# 2.net
KiCad netlist of a schematic drawn in EAGLE
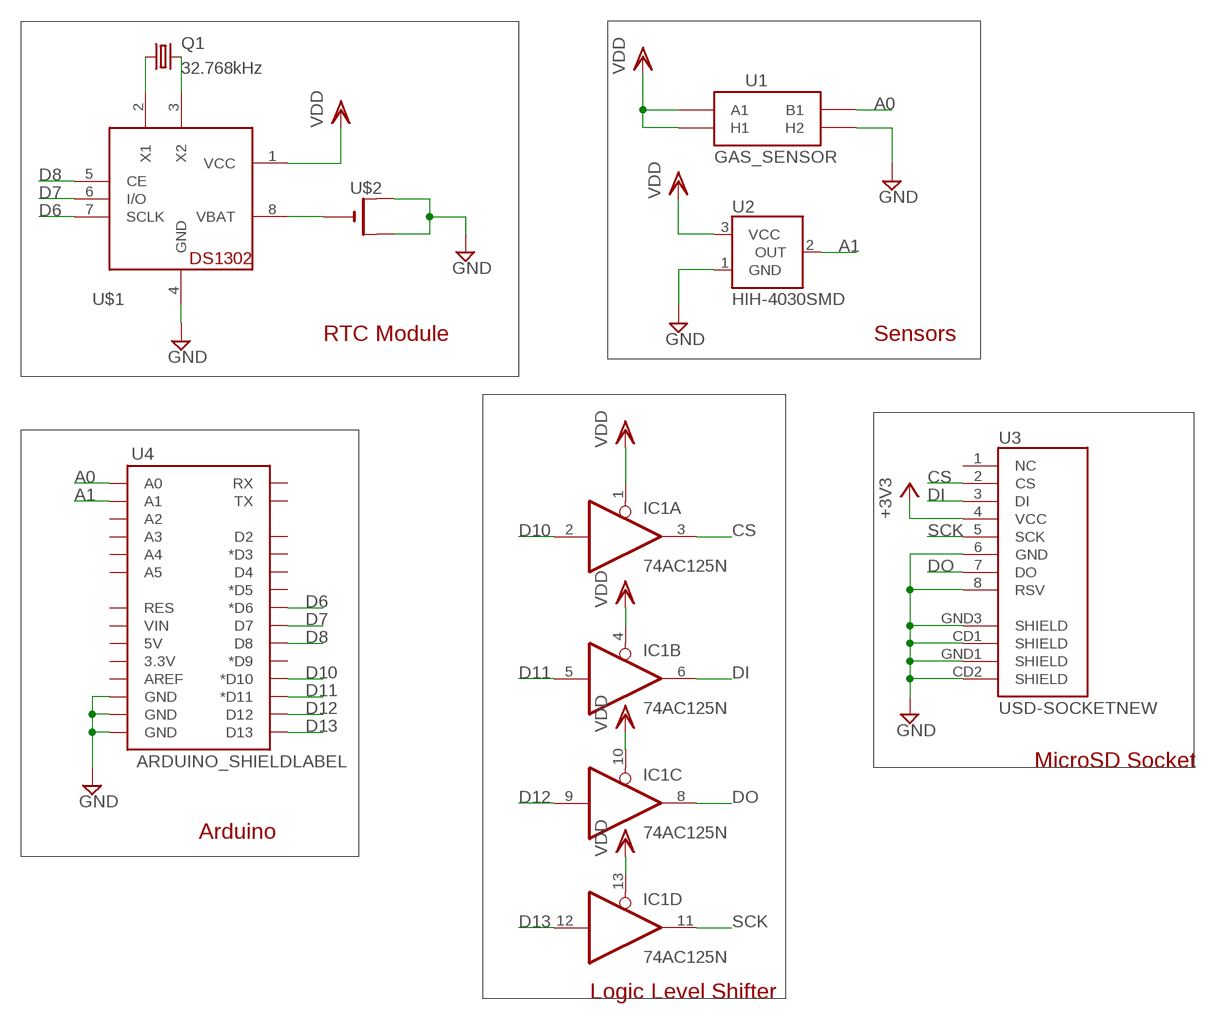
[diagram p0: schematic, sheet 1]

(export (version "E")
  (design (tool "Eeschema 10.0.6"))
  (components
    (comp (ref "IC1")
      (value "74AC125N")
      (footprint "eagle-import:DIL14")
      (libsource (lib "eagle-import") (part "74125NAC"))
    )
    (comp (ref "Q1")
      (value "32.768kHz")
      (footprint "eagle-import:TC38H")
      (libsource (lib "eagle-import") (part "CRYSTALTC38H"))
    )
    (comp (ref "U$1")
      (value "DS1302")
      (footprint "eagle-import:DIL08-ROUND")
      (libsource (lib "eagle-import") (part "DS1302"))
    )
    (comp (ref "U$2")
      (value "CR2032THM")
      (footprint "eagle-import:CR2032-THRU")
      (libsource (lib "eagle-import") (part "CR2032THM"))
    )
    (comp (ref "U1")
      (value "GAS_SENSOR")
      (footprint "eagle-import:MQ-3")
      (libsource (lib "eagle-import") (part "GAS_SENSOR"))
    )
    (comp (ref "U2")
      (value "HIH-4030SMD")
      (footprint "eagle-import:HIH-4030")
      (libsource (lib "eagle-import") (part "HIH-4030SMD"))
    )
    (comp (ref "U3")
      (value "USD-SOCKETNEW")
      (footprint "eagle-import:MICRO-SD-SOCKET-PP")
      (libsource (lib "eagle-import") (part "USD-SOCKETNEW"))
    )
    (comp (ref "U4")
      (value "ARDUINO_SHIELDLABEL")
      (footprint "eagle-import:DUEMILANOVE_SHIELD")
      (libsource (lib "eagle-import") (part "ARDUINO_SHIELDLABEL"))
    )
  )
  (nets
    (net (code "1") (name "+3V3") (class "Default")
      (node (ref "U3") (pin "4") (pinfunction "VCC_4") (pintype "bidirectional"))
    )
    (net (code "2") (name "/A0") (class "Default")
      (node (ref "U1") (pin "B1") (pinfunction "B1_B1") (pintype "bidirectional"))
      (node (ref "U4") (pin "A0") (pinfunction "A0_A0") (pintype "bidirectional"))
    )
    (net (code "3") (name "/A1") (class "Default")
      (node (ref "U2") (pin "2") (pinfunction "OUT_2") (pintype "bidirectional"))
      (node (ref "U4") (pin "A1") (pinfunction "A1_A1") (pintype "bidirectional"))
    )
    (net (code "4") (name "/CS") (class "Default")
      (node (ref "IC1") (pin "3") (pinfunction "O_3") (pintype "tri_state"))
      (node (ref "U3") (pin "2") (pinfunction "CS_2") (pintype "bidirectional"))
    )
    (net (code "5") (name "/D6") (class "Default")
      (node (ref "U$1") (pin "7") (pinfunction "SCLK_7") (pintype "input"))
      (node (ref "U4") (pin "D6") (pinfunction "*D6_D6") (pintype "bidirectional"))
    )
    (net (code "6") (name "/D7") (class "Default")
      (node (ref "U$1") (pin "6") (pinfunction "I/O_6") (pintype "bidirectional"))
      (node (ref "U4") (pin "D7") (pinfunction "D7_D7") (pintype "bidirectional"))
    )
    (net (code "7") (name "/D8") (class "Default")
      (node (ref "U$1") (pin "5") (pinfunction "CE_5") (pintype "input"))
      (node (ref "U4") (pin "D8") (pinfunction "D8_D8") (pintype "bidirectional"))
    )
    (net (code "8") (name "/D10") (class "Default")
      (node (ref "IC1") (pin "2") (pinfunction "I_2") (pintype "input"))
      (node (ref "U4") (pin "D10") (pinfunction "*D10_D10") (pintype "bidirectional"))
    )
    (net (code "9") (name "/D11") (class "Default")
      (node (ref "IC1") (pin "5") (pinfunction "I_5") (pintype "input"))
      (node (ref "U4") (pin "D11") (pinfunction "*D11_D11") (pintype "bidirectional"))
    )
    (net (code "10") (name "/D12") (class "Default")
      (node (ref "IC1") (pin "9") (pinfunction "I_9") (pintype "input"))
      (node (ref "U4") (pin "D12") (pinfunction "D12_D12") (pintype "bidirectional"))
    )
    (net (code "11") (name "/D13") (class "Default")
      (node (ref "IC1") (pin "12") (pinfunction "I_12") (pintype "input"))
      (node (ref "U4") (pin "D13") (pinfunction "D13_D13") (pintype "bidirectional"))
    )
    (net (code "12") (name "/DI") (class "Default")
      (node (ref "IC1") (pin "6") (pinfunction "O_6") (pintype "tri_state"))
      (node (ref "U3") (pin "3") (pinfunction "DI_3") (pintype "bidirectional"))
    )
    (net (code "13") (name "/DO") (class "Default")
      (node (ref "IC1") (pin "8") (pinfunction "O_8") (pintype "tri_state"))
      (node (ref "U3") (pin "7") (pinfunction "DO_7") (pintype "bidirectional"))
    )
    (net (code "14") (name "/SCK") (class "Default")
      (node (ref "IC1") (pin "11") (pinfunction "O_11") (pintype "tri_state"))
      (node (ref "U3") (pin "5") (pinfunction "SCK_5") (pintype "bidirectional"))
    )
    (net (code "15") (name "GND") (class "Default")
      (node (ref "U$1") (pin "4") (pinfunction "GND_4") (pintype "power_in"))
      (node (ref "U$2") (pin "+1") (pinfunction "+_+1") (pintype "passive"))
      (node (ref "U$2") (pin "+2") (pinfunction "+1_+2") (pintype "passive"))
      (node (ref "U1") (pin "HB") (pinfunction "H2_HB") (pintype "bidirectional"))
      (node (ref "U2") (pin "1") (pinfunction "GND_1") (pintype "bidirectional"))
      (node (ref "U3") (pin "6") (pinfunction "GND_6") (pintype "bidirectional"))
      (node (ref "U3") (pin "8") (pinfunction "RSV_8") (pintype "bidirectional"))
      (node (ref "U3") (pin "CD1") (pinfunction "SHIELD_CD1") (pintype "bidirectional"))
      (node (ref "U3") (pin "CD2") (pinfunction "SHIELD_CD2") (pintype "bidirectional"))
      (node (ref "U3") (pin "GND1") (pinfunction "SHIELD_GND1") (pintype "bidirectional"))
      (node (ref "U3") (pin "GND3") (pinfunction "SHIELD_GND3") (pintype "bidirectional"))
      (node (ref "U4") (pin "GND@0") (pinfunction "GND_GND@0") (pintype "bidirectional"))
      (node (ref "U4") (pin "GND@1") (pinfunction "GND_GND@1") (pintype "bidirectional"))
      (node (ref "U4") (pin "GND@2") (pinfunction "GND_GND@2") (pintype "bidirectional"))
    )
    (net (code "16") (name "Net-(U$1-VBAT)") (class "Default")
      (node (ref "U$1") (pin "8") (pinfunction "VBAT_8") (pintype "power_in"))
      (node (ref "U$2") (pin "-") (pinfunction "-_-") (pintype "passive"))
    )
    (net (code "17") (name "Net-(U$1-X1)") (class "Default")
      (node (ref "Q1") (pin "1") (pinfunction "1_1") (pintype "passive"))
      (node (ref "U$1") (pin "2") (pinfunction "X1_2") (pintype "passive"))
    )
    (net (code "18") (name "Net-(U$1-X2)") (class "Default")
      (node (ref "Q1") (pin "2") (pinfunction "2_2") (pintype "passive"))
      (node (ref "U$1") (pin "3") (pinfunction "X2_3") (pintype "passive"))
    )
    (net (code "19") (name "VDD") (class "Default")
      (node (ref "IC1") (pin "1") (pinfunction "OE_1") (pintype "input"))
      (node (ref "IC1") (pin "10") (pinfunction "OE_10") (pintype "input"))
      (node (ref "IC1") (pin "13") (pinfunction "OE_13") (pintype "input"))
      (node (ref "IC1") (pin "4") (pinfunction "OE_4") (pintype "input"))
      (node (ref "U$1") (pin "1") (pinfunction "VCC_1") (pintype "power_in"))
      (node (ref "U1") (pin "A1") (pinfunction "A1_A1") (pintype "bidirectional"))
      (node (ref "U1") (pin "HA") (pinfunction "H1_HA") (pintype "bidirectional"))
      (node (ref "U2") (pin "3") (pinfunction "VCC_3") (pintype "bidirectional"))
    )
    (net (code "20") (name "unconnected-(U3-NC-Pad1)") (class "Default")
      (node (ref "U3") (pin "1") (pinfunction "NC_1") (pintype "bidirectional"))
    )
    (net (code "21") (name "unconnected-(U4-*D3-PadD3)") (class "Default")
      (node (ref "U4") (pin "D3") (pinfunction "*D3_D3") (pintype "bidirectional"))
    )
    (net (code "22") (name "unconnected-(U4-*D5-PadD5)") (class "Default")
      (node (ref "U4") (pin "D5") (pinfunction "*D5_D5") (pintype "bidirectional"))
    )
    (net (code "23") (name "unconnected-(U4-*D9-PadD9)") (class "Default")
      (node (ref "U4") (pin "D9") (pinfunction "*D9_D9") (pintype "bidirectional"))
    )
    (net (code "24") (name "unconnected-(U4-Pad3.3V)") (class "Default")
      (node (ref "U4") (pin "3.3V") (pinfunction "3.3V_3.3V") (pintype "bidirectional"))
    )
    (net (code "25") (name "unconnected-(U4-Pad5V)") (class "Default")
      (node (ref "U4") (pin "5V") (pinfunction "5V_5V") (pintype "bidirectional"))
    )
    (net (code "26") (name "unconnected-(U4-PadA2)") (class "Default")
      (node (ref "U4") (pin "A2") (pinfunction "A2_A2") (pintype "bidirectional"))
    )
    (net (code "27") (name "unconnected-(U4-PadA3)") (class "Default")
      (node (ref "U4") (pin "A3") (pinfunction "A3_A3") (pintype "bidirectional"))
    )
    (net (code "28") (name "unconnected-(U4-PadA4)") (class "Default")
      (node (ref "U4") (pin "A4") (pinfunction "A4_A4") (pintype "bidirectional"))
    )
    (net (code "29") (name "unconnected-(U4-PadA5)") (class "Default")
      (node (ref "U4") (pin "A5") (pinfunction "A5_A5") (pintype "bidirectional"))
    )
    (net (code "30") (name "unconnected-(U4-PadAREF)") (class "Default")
      (node (ref "U4") (pin "AREF") (pinfunction "AREF_AREF") (pintype "bidirectional"))
    )
    (net (code "31") (name "unconnected-(U4-PadD2)") (class "Default")
      (node (ref "U4") (pin "D2") (pinfunction "D2_D2") (pintype "bidirectional"))
    )
    (net (code "32") (name "unconnected-(U4-PadD4)") (class "Default")
      (node (ref "U4") (pin "D4") (pinfunction "D4_D4") (pintype "bidirectional"))
    )
    (net (code "33") (name "unconnected-(U4-PadRES)") (class "Default")
      (node (ref "U4") (pin "RES") (pinfunction "RES_RES") (pintype "bidirectional"))
    )
    (net (code "34") (name "unconnected-(U4-PadRX)") (class "Default")
      (node (ref "U4") (pin "RX") (pinfunction "RX_RX") (pintype "bidirectional"))
    )
    (net (code "35") (name "unconnected-(U4-PadTX)") (class "Default")
      (node (ref "U4") (pin "TX") (pinfunction "TX_TX") (pintype "bidirectional"))
    )
    (net (code "36") (name "unconnected-(U4-PadVIN)") (class "Default")
      (node (ref "U4") (pin "VIN") (pinfunction "VIN_VIN") (pintype "bidirectional"))
    )
  )
)
